# Input_Protection.net
KiCad netlist of a schematic drawn in Altium Designer
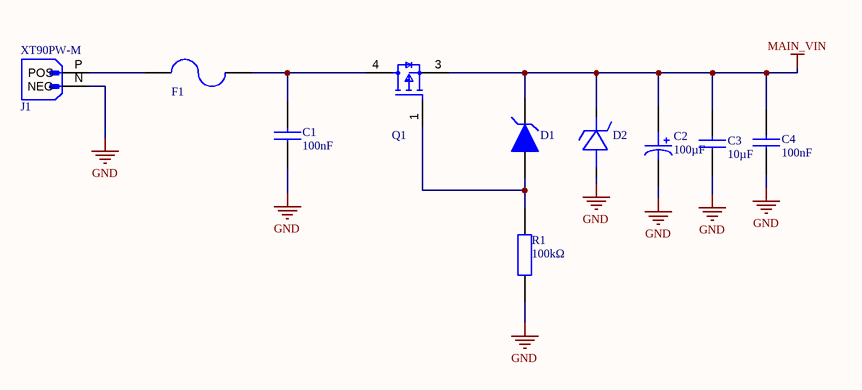
[diagram p0: Input_Protection.SchDoc]

(export (version "E")
  (design (tool "Eeschema 10.0.6"))
  (components
    (comp (ref "C1")
      (value "100nF")
      (footprint "CAP_0603")
      (description "CGA Series 0603 100 nF 50 V ±10 % Tolerance X7R SMT Multilayer Ceramic Capacitor")
      (fields
        (field (name "MANUFACTURER") "TDK")
        (field (name "MANUFACTURER PART NUMBER") "CGA3E2X7R1H104K080AA")
      )
      (libsource (lib "PDU_BOM") (part "CGA3E2X7R1H104K080AA"))
    )
    (comp (ref "C2")
      (value "100µF")
      (footprint "CAP ALUM SMD")
      (description "Conductive Polymer Hybrid Aluminum Electrolytic Capacitors, 100µF, 35V, -55 to 105¡C")
      (fields
        (field (name "MANUFACTURER") "Panasonic")
        (field (name "MANUFACTURER PART NUMBER") "EEH-ZA1V101P")
      )
      (libsource (lib "PDU_BOM") (part "EEH-ZA1V101P"))
    )
    (comp (ref "C3")
      (value "10µF")
      (footprint "CAP_1206")
      (description "50V 10uF X7R 卤10% 1206 Multilayer Ceramic Capacitors MLCC - SMD/SMT ROHS")
      (fields
        (field (name "MANUFACTURER") "TDK")
        (field (name "MANUFACTURER PART NUMBER") "C3216X7R1H106K160AC")
      )
      (libsource (lib "PDU_BOM") (part "C3216X7R1H106K160AC"))
    )
    (comp (ref "C4")
      (value "100nF")
      (footprint "CAP_0603")
      (description "CGA Series 0603 100 nF 50 V ±10 % Tolerance X7R SMT Multilayer Ceramic Capacitor")
      (fields
        (field (name "MANUFACTURER") "TDK")
        (field (name "MANUFACTURER PART NUMBER") "CGA3E2X7R1H104K080AA")
      )
      (libsource (lib "PDU_BOM") (part "CGA3E2X7R1H104K080AA"))
    )
    (comp (ref "D1")
      (value "BZT52C15")
      (footprint "SOD323")
      (description "BZT52C15S Series 200 mW 15 V 10 mA Surface Mount Zener Diode - SOD-323")
      (fields
        (field (name "MANUFACTURER") "Diodes Inc.")
        (field (name "MANUFACTURER PART NUMBER") "BZT52C15S-7-F")
      )
      (libsource (lib "PDU_BOM") (part "BZT52C15"))
    )
    (comp (ref "D2")
      (value "SMCJ58A")
      (footprint "SMC (DO-214AB)")
      (description "Diode TVS Single Uni-Directional 58V 1.5kW 2-Pin DO-214AB")
      (fields (field (name "MANUFACTURER") "Taiwan Semiconductor"))
      (libsource (lib "PDU_BOM") (part "SMCJ58A"))
    )
    (comp (ref "F1")
      (value "Littelfuse 0452010.MRL")
      (footprint "FUSE_2410")
      (description "Electric Fuse, Time Lag Blow, 10A, 72VAC, 60VDC, 50A (IR), Surface Mount, NANO")
      (fields
        (field (name "MANUFACTURER") "Littelfuse")
        (field (name "MANUFACTURER PART NUMBER") "0452010.MRL")
      )
      (libsource (lib "PDU_BOM") (part "Littelfuse 0452010.MRL"))
    )
    (comp (ref "J1")
      (value "XT90PW-M")
      (footprint "XT90PW-M")
      (description "Socket; DC supply; XT90; male; PIN: 2; on PCBs; THT; Colour: yellow")
      (fields (field (name "MANUFACTURER") "Amass"))
      (libsource (lib "PDU_BOM") (part "XT90PW-M"))
    )
    (comp (ref "Q1")
      (value "SQM120P06-07L")
      (footprint "D2PAK")
      (description "MOSFET P-CH 60V 120A TO263 / Trans MOSFET P-CH 60V 120A Automotive 3-Pin(2+Tab) D2PAK")
      (fields
        (field (name "MANUFACTURER") "Vishay")
        (field (name "MANUFACTURER PART NUMBER") "SQM120P06-07L_GE3")
      )
      (libsource (lib "PDU_BOM") (part "SQM120P06-07L"))
    )
    (comp (ref "R1")
      (value "100kΩ")
      (footprint "RES_0603")
      (description "Res Thick Film 0603 100K Ohm 1% 1/3W ±100ppm/°C Molded SMD SMD Paper T/R")
      (fields
        (field (name "MANUFACTURER") "Vishay")
        (field (name "MANUFACTURER PART NUMBER") "CRCW0603100KFKEAHP")
      )
      (libsource (lib "PDU_BOM") (part "CRCW0603100KFKEA"))
    )
  )
  (nets
    (net (code "1") (name "GND") (class "Default")
      (node (ref "C1") (pin "1") (pinfunction "1_1") (pintype "passive"))
      (node (ref "C2") (pin "2") (pinfunction "A_2") (pintype "passive"))
      (node (ref "C3") (pin "1") (pinfunction "1_1") (pintype "passive"))
      (node (ref "C4") (pin "1") (pinfunction "1_1") (pintype "passive"))
      (node (ref "D2") (pin "2") (pinfunction "2_2") (pintype "passive"))
      (node (ref "J1") (pin "N") (pinfunction "NEG_N") (pintype "passive"))
      (node (ref "R1") (pin "1") (pinfunction "1_1") (pintype "passive"))
    )
    (net (code "2") (name "MAIN_VIN") (class "Default")
      (node (ref "C2") (pin "1") (pinfunction "C_1") (pintype "passive"))
      (node (ref "C3") (pin "2") (pinfunction "2_2") (pintype "passive"))
      (node (ref "C4") (pin "2") (pinfunction "2_2") (pintype "passive"))
      (node (ref "D1") (pin "1") (pinfunction "1_1") (pintype "passive"))
      (node (ref "D2") (pin "1") (pinfunction "1_1") (pintype "passive"))
      (node (ref "Q1") (pin "3") (pinfunction "S_3") (pintype "passive"))
    )
    (net (code "3") (name "Net-(J1-POS)") (class "Default")
      (node (ref "F1") (pin "1") (pinfunction "1_1") (pintype "passive"))
      (node (ref "J1") (pin "P") (pinfunction "POS_P") (pintype "passive"))
    )
    (net (code "4") (name "Net-(Q1-D)") (class "Default")
      (node (ref "C1") (pin "2") (pinfunction "2_2") (pintype "passive"))
      (node (ref "F1") (pin "2") (pinfunction "2_2") (pintype "passive"))
      (node (ref "Q1") (pin "4") (pinfunction "D_4") (pintype "passive"))
    )
    (net (code "5") (name "Net-(Q1-G)") (class "Default")
      (node (ref "D1") (pin "2") (pinfunction "2_2") (pintype "passive"))
      (node (ref "Q1") (pin "1") (pinfunction "G_1") (pintype "passive"))
      (node (ref "R1") (pin "2") (pinfunction "2_2") (pintype "passive"))
    )
  )
)
